# ARS_CR_LedStripModule_Rev1B.net
KiCad netlist of a schematic drawn in Altium Designer
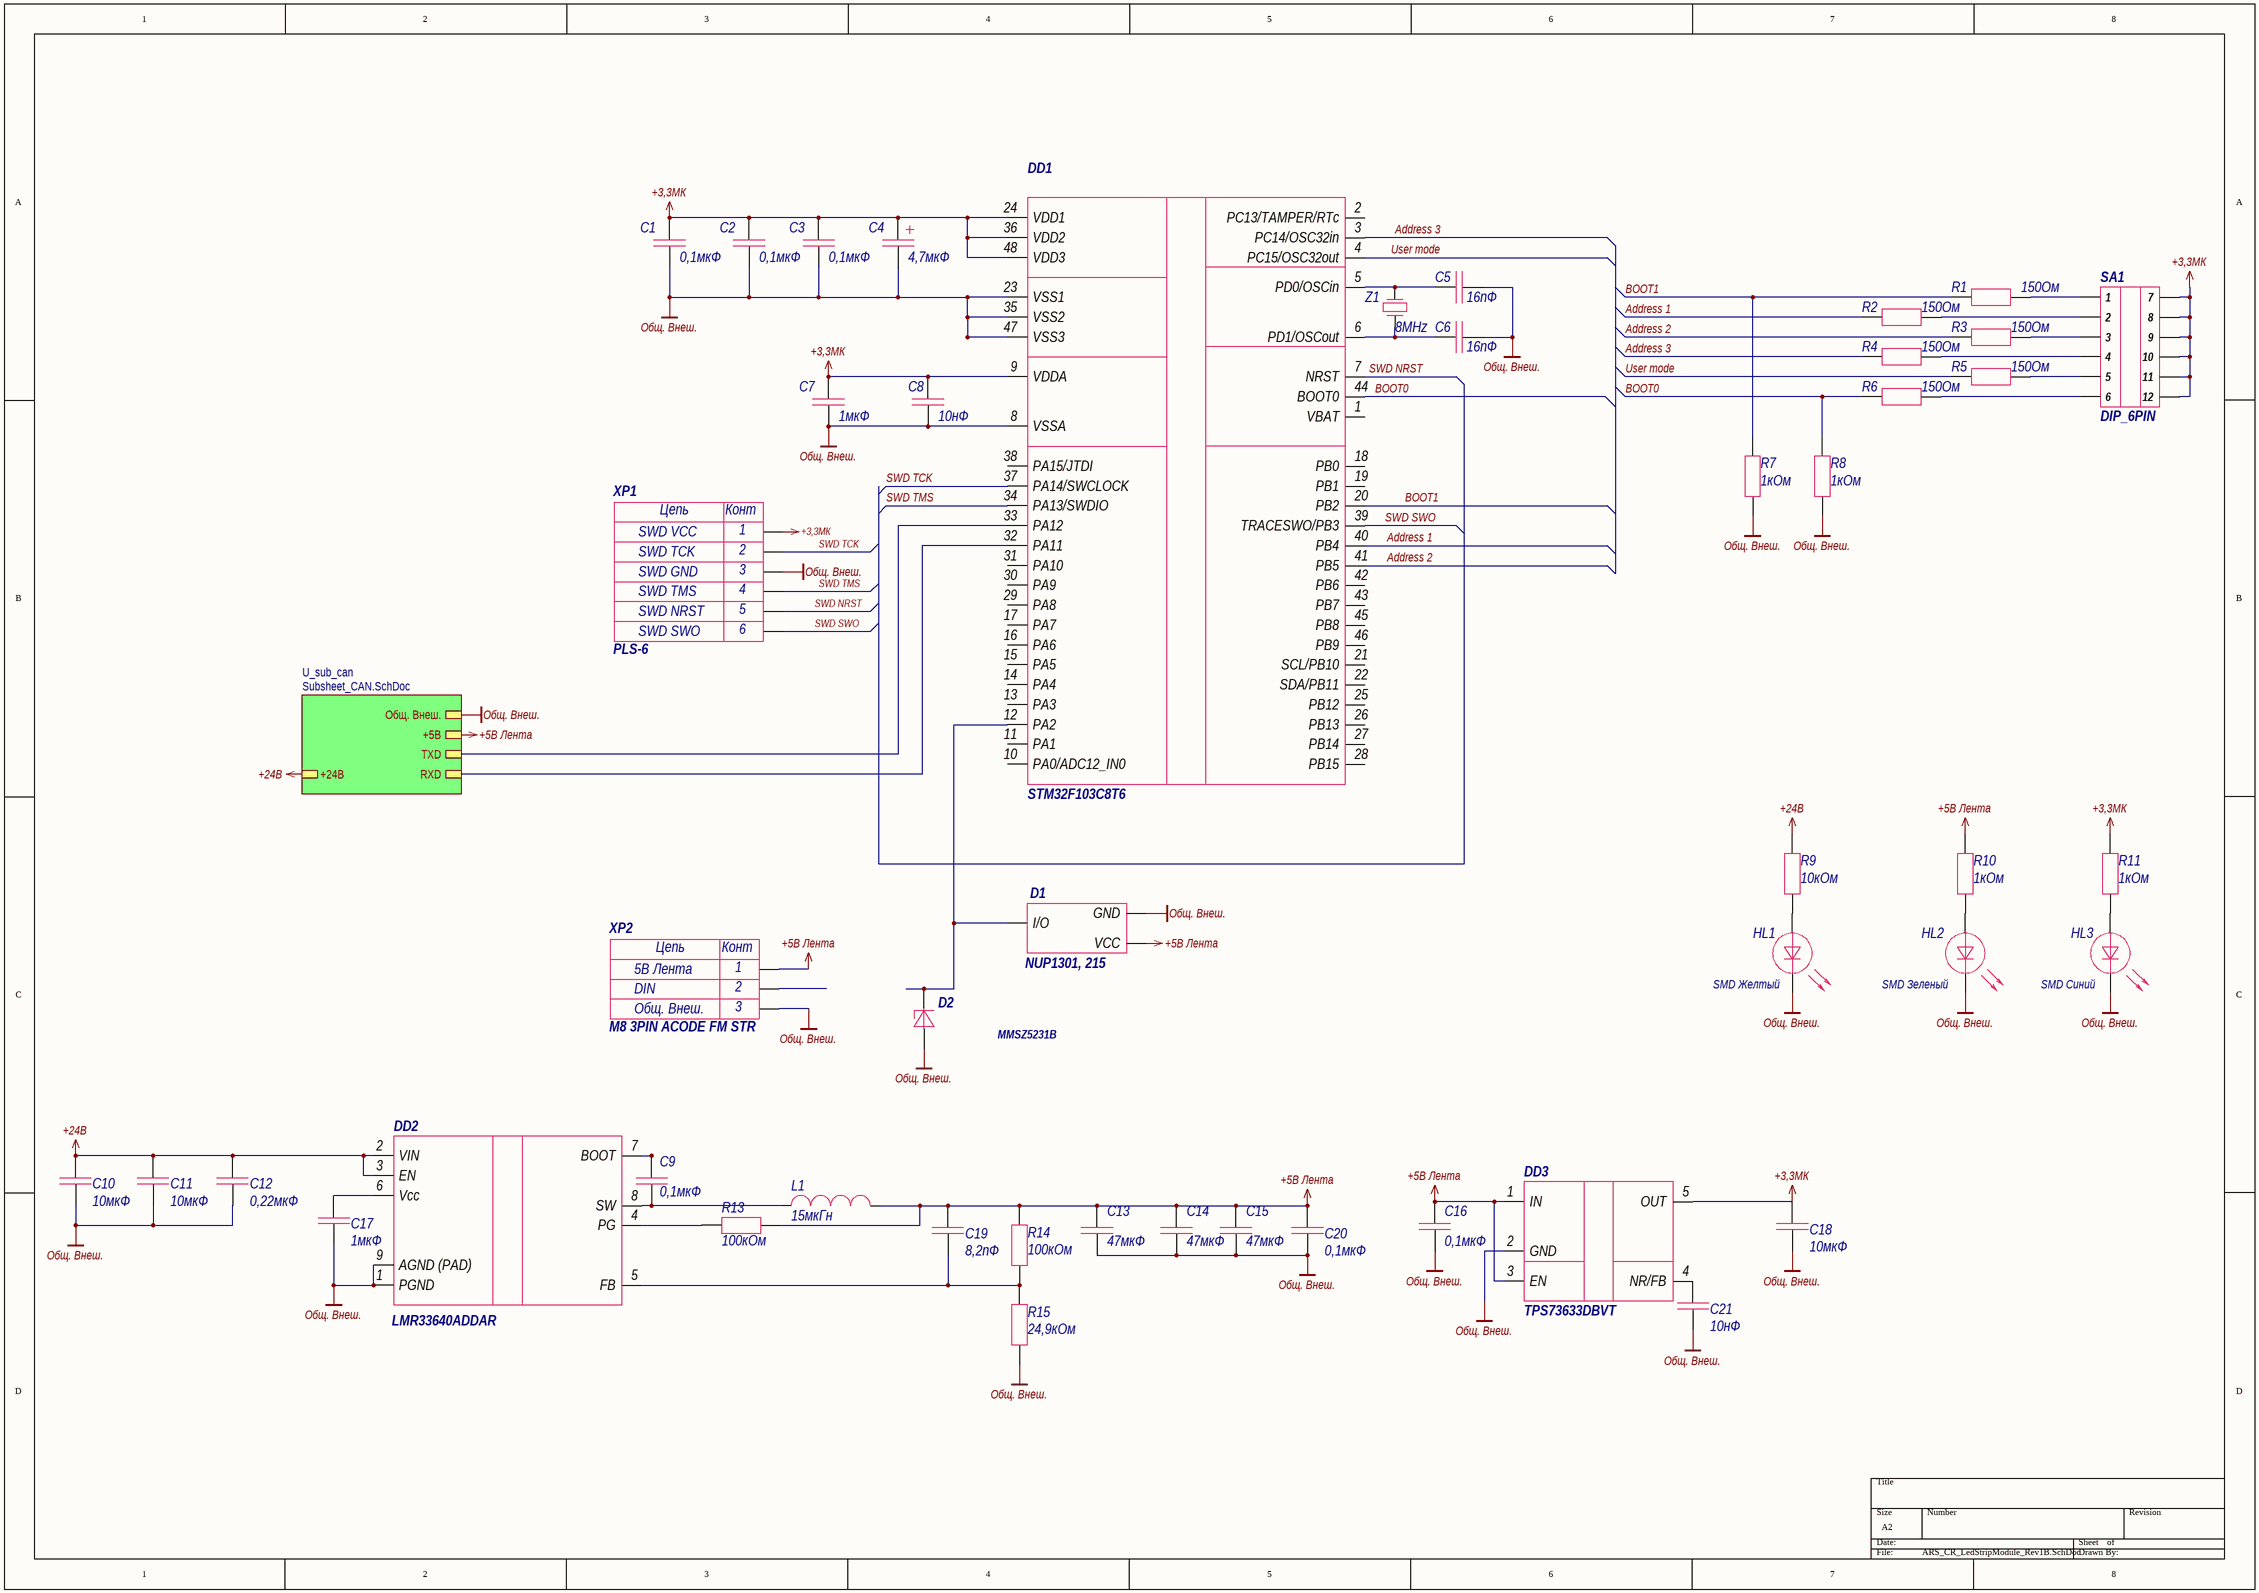
[diagram p0: ARS_CR_LedStripModule_Rev1B.SchDoc]

(export (version "E")
  (design (tool "Eeschema 10.0.6"))
  (components
    (comp (ref "C1")
      (value "0,1мкФ")
      (footprint "0603C")
      (fields (field (name "TOLERANCE") "10%") (field (name "Comment") "Capacitor"))
      (libsource (lib "Database_Maltsev") (part "Capacitor"))
    )
    (comp (ref "C2")
      (value "0,1мкФ")
      (footprint "0603C")
      (fields (field (name "TOLERANCE") "10%") (field (name "Comment") "Capacitor"))
      (libsource (lib "Database_Maltsev") (part "Capacitor"))
    )
    (comp (ref "C3")
      (value "0,1мкФ")
      (footprint "0603C")
      (fields (field (name "TOLERANCE") "10%") (field (name "Comment") "Capacitor"))
      (libsource (lib "Database_Maltsev") (part "Capacitor"))
    )
    (comp (ref "C4")
      (value "4,7мкФ")
      (footprint "TC_A (3216)")
      (fields (field (name "TOLERANCE") "10%") (field (name "Comment") "1uF"))
      (libsource (lib "Database_Maltsev") (part "Capacitor Polarized"))
    )
    (comp (ref "C5")
      (value "16пФ")
      (footprint "0603C")
      (fields (field (name "TOLERANCE") "5%") (field (name "Comment") "Capacitor"))
      (libsource (lib "Database_Maltsev") (part "Capacitor"))
    )
    (comp (ref "C6")
      (value "16пФ")
      (footprint "0603C")
      (fields (field (name "TOLERANCE") "5%") (field (name "Comment") "Capacitor"))
      (libsource (lib "Database_Maltsev") (part "Capacitor"))
    )
    (comp (ref "C7")
      (value "1мкФ")
      (footprint "0603C")
      (fields (field (name "TOLERANCE") "10%") (field (name "Comment") "Capacitor"))
      (libsource (lib "Database_Maltsev") (part "Capacitor"))
    )
    (comp (ref "C8")
      (value "10нФ")
      (footprint "0603C")
      (fields (field (name "TOLERANCE") "10%") (field (name "Comment") "Capacitor"))
      (libsource (lib "Database_Maltsev") (part "Capacitor"))
    )
    (comp (ref "C9")
      (value "0,1мкФ")
      (footprint "0603C")
      (fields (field (name "TOLERANCE") "10%") (field (name "Comment") "Capacitor"))
      (libsource (lib "Database_Maltsev") (part "Capacitor"))
    )
    (comp (ref "C10")
      (value "10мкФ")
      (footprint "1210C")
      (fields (field (name "TOLERANCE") "20%") (field (name "Comment") "Capacitor"))
      (libsource (lib "Database_Maltsev") (part "Capacitor"))
    )
    (comp (ref "C11")
      (value "10мкФ")
      (footprint "1210C")
      (fields (field (name "TOLERANCE") "20%") (field (name "Comment") "Capacitor"))
      (libsource (lib "Database_Maltsev") (part "Capacitor"))
    )
    (comp (ref "C12")
      (value "0,22мкФ")
      (footprint "0603C")
      (fields (field (name "TOLERANCE") "5%") (field (name "Comment") "Capacitor"))
      (libsource (lib "Database_Maltsev") (part "Capacitor"))
    )
    (comp (ref "C13")
      (value "47мкФ")
      (footprint "1210C")
      (fields (field (name "TOLERANCE") "10%") (field (name "Comment") "Capacitor"))
      (libsource (lib "Database_Maltsev") (part "Capacitor"))
    )
    (comp (ref "C14")
      (value "47мкФ")
      (footprint "1210C")
      (fields (field (name "TOLERANCE") "10%") (field (name "Comment") "Capacitor"))
      (libsource (lib "Database_Maltsev") (part "Capacitor"))
    )
    (comp (ref "C15")
      (value "47мкФ")
      (footprint "1210C")
      (fields (field (name "TOLERANCE") "10%") (field (name "Comment") "Capacitor"))
      (libsource (lib "Database_Maltsev") (part "Capacitor"))
    )
    (comp (ref "C16")
      (value "0,1мкФ")
      (footprint "0603C")
      (fields (field (name "TOLERANCE") "10%") (field (name "Comment") "Capacitor"))
      (libsource (lib "Database_Maltsev") (part "Capacitor"))
    )
    (comp (ref "C17")
      (value "1мкФ")
      (footprint "0603C")
      (fields (field (name "TOLERANCE") "10%") (field (name "Comment") "Capacitor"))
      (libsource (lib "Database_Maltsev") (part "Capacitor"))
    )
    (comp (ref "C18")
      (value "10мкФ")
      (footprint "0805C")
      (fields (field (name "TOLERANCE") "10%") (field (name "Comment") "Capacitor"))
      (libsource (lib "Database_Maltsev") (part "Capacitor"))
    )
    (comp (ref "C19")
      (value "8,2пФ")
      (footprint "0603C")
      (fields (field (name "TOLERANCE") "3%") (field (name "Comment") "Capacitor"))
      (libsource (lib "Database_Maltsev") (part "Capacitor"))
    )
    (comp (ref "C20")
      (value "0,1мкФ")
      (footprint "0603C")
      (fields (field (name "TOLERANCE") "10%") (field (name "Comment") "Capacitor"))
      (libsource (lib "Database_Maltsev") (part "Capacitor"))
    )
    (comp (ref "C21")
      (value "10нФ")
      (footprint "0603C")
      (fields (field (name "TOLERANCE") "10%") (field (name "Comment") "Capacitor"))
      (libsource (lib "Database_Maltsev") (part "Capacitor"))
    )
    (comp (ref "D1")
      (value "NUP1301, 215")
      (footprint "SOT23")
      (description "TVS")
      (libsource (lib "Database_Maltsev") (part "NUP1301,215"))
    )
    (comp (ref "D2")
      (value "Zener_Diode")
      (footprint "SOD-123FL")
      (libsource (lib "Database_Maltsev") (part "Zener_Diode"))
    )
    (comp (ref "DD1")
      (value "STM32F103C8T6")
      (footprint "LQFP48")
      (description "STM 32-bit MCU")
      (fields (field (name "DESIGNER STATUS") "Tested and Approved"))
      (libsource (lib "Database_Maltsev") (part "STM32F103C8T6"))
    )
    (comp (ref "DD2")
      (value "LMR33640ADDAR")
      (footprint "SOIC-9N")
      (fields (field (name "PART NAME") "LMR33640ADDAR"))
      (libsource (lib "Database_Maltsev") (part "LMR33640ADDAR"))
    )
    (comp (ref "DD3")
      (value "TPS73633DBVT")
      (footprint "SOT23-5L")
      (fields (field (name "PART NAME") "TPS73633DBVT"))
      (libsource (lib "Database_Maltsev") (part "TPS73633DBVT"))
    )
    (comp (ref "HL1")
      (value "SMD Желтый")
      (footprint "0805D")
      (description "Желтый")
      (libsource (lib "Database_Maltsev") (part "LED"))
    )
    (comp (ref "HL2")
      (value "SMD Зеленый")
      (footprint "0805D")
      (description "Зеленый")
      (libsource (lib "Database_Maltsev") (part "LED"))
    )
    (comp (ref "HL3")
      (value "SMD Синий")
      (footprint "0805D")
      (description "Синий")
      (libsource (lib "Database_Maltsev") (part "LED"))
    )
    (comp (ref "L1")
      (value "15мкГн")
      (footprint "induct_12,3x12,3x8")
      (fields (field (name "TOLERANCE") "20%") (field (name "Comment") "Inductance"))
      (libsource (lib "Database_Maltsev") (part "Inductance"))
    )
    (comp (ref "R1")
      (value "150Ом")
      (footprint "0603R")
      (fields (field (name "TOLERANCE") "1%") (field (name "Comment") "Resistor"))
      (libsource (lib "Database_Maltsev") (part "Resistor"))
    )
    (comp (ref "R2")
      (value "150Ом")
      (footprint "0603R")
      (fields (field (name "TOLERANCE") "1%") (field (name "Comment") "Resistor"))
      (libsource (lib "Database_Maltsev") (part "Resistor"))
    )
    (comp (ref "R3")
      (value "150Ом")
      (footprint "0603R")
      (fields (field (name "TOLERANCE") "1%") (field (name "Comment") "Resistor"))
      (libsource (lib "Database_Maltsev") (part "Resistor"))
    )
    (comp (ref "R4")
      (value "150Ом")
      (footprint "0603R")
      (fields (field (name "TOLERANCE") "1%") (field (name "Comment") "Resistor"))
      (libsource (lib "Database_Maltsev") (part "Resistor"))
    )
    (comp (ref "R5")
      (value "150Ом")
      (footprint "0603R")
      (fields (field (name "TOLERANCE") "1%") (field (name "Comment") "Resistor"))
      (libsource (lib "Database_Maltsev") (part "Resistor"))
    )
    (comp (ref "R6")
      (value "150Ом")
      (footprint "0603R")
      (fields (field (name "TOLERANCE") "1%") (field (name "Comment") "Resistor"))
      (libsource (lib "Database_Maltsev") (part "Resistor"))
    )
    (comp (ref "R7")
      (value "1кОм")
      (footprint "0603R")
      (fields (field (name "TOLERANCE") "5%") (field (name "Comment") "Resistor"))
      (libsource (lib "") (part "Resistor_1"))
    )
    (comp (ref "R8")
      (value "1кОм")
      (footprint "0603R")
      (fields (field (name "TOLERANCE") "5%") (field (name "Comment") "Resistor"))
      (libsource (lib "") (part "Resistor_1"))
    )
    (comp (ref "R9")
      (value "10кОм")
      (footprint "0603R")
      (fields (field (name "TOLERANCE") "5%") (field (name "Comment") "Resistor"))
      (libsource (lib "") (part "Resistor_1"))
    )
    (comp (ref "R10")
      (value "1кОм")
      (footprint "0603R")
      (fields (field (name "TOLERANCE") "5%") (field (name "Comment") "Resistor"))
      (libsource (lib "") (part "Resistor_1"))
    )
    (comp (ref "R11")
      (value "1кОм")
      (footprint "0603R")
      (fields (field (name "TOLERANCE") "5%") (field (name "Comment") "Resistor"))
      (libsource (lib "") (part "Resistor_1"))
    )
    (comp (ref "R13")
      (value "100кОм")
      (footprint "0603R")
      (fields (field (name "TOLERANCE") "1%") (field (name "Comment") "Resistor"))
      (libsource (lib "Database_Maltsev") (part "Resistor"))
    )
    (comp (ref "R14")
      (value "100кОм")
      (footprint "0603R")
      (fields (field (name "TOLERANCE") "1%") (field (name "Comment") "Resistor"))
      (libsource (lib "") (part "Resistor_1"))
    )
    (comp (ref "R15")
      (value "24,9кОм")
      (footprint "0603R")
      (fields (field (name "TOLERANCE") "1%") (field (name "Comment") "Resistor"))
      (libsource (lib "") (part "Resistor_1"))
    )
    (comp (ref "SA1")
      (value "DIP_6PIN")
      (footprint "SW-6")
      (description "SMD")
      (libsource (lib "Database_Maltsev") (part "DIP_6PIN"))
    )
    (comp (ref "XP1")
      (value "PLS-6")
      (footprint "PLS6")
      (description "Male")
      (fields
        (field (name "VALUE1") "SWD VCC")
        (field (name "VALUE2") "SWD TCK")
        (field (name "VALUE3") "SWD GND")
        (field (name "VALUE4") "SWD TMS")
        (field (name "VALUE5") "SWD NRST")
        (field (name "VALUE6") "SWD SWO")
        (field (name "Comment") "6_PIN_XP")
      )
      (libsource (lib "Database_Maltsev") (part "6_PIN_XP"))
    )
    (comp (ref "XP2")
      (value "M8 3PIN ACODE FM STR")
      (footprint "M8_ACODE_3PIN_FM_STR")
      (description "A code ; Female ; Front mount")
      (fields
        (field (name "VALUE1") "5В Лента")
        (field (name "VALUE2") "DIN")
        (field (name "VALUE3") "Общ. Внеш.")
        (field (name "TOLERANCE") "straight")
        (field (name "Comment") "3_PIN_XP")
      )
      (libsource (lib "Database_Maltsev") (part "3_PIN_XP"))
    )
    (comp (ref "Z1")
      (value "8MHz")
      (footprint "HC49US")
      (description "Резонатор")
      (fields (field (name "Comment") "XTAL"))
      (libsource (lib "Database_Maltsev") (part "XTAL"))
    )
  )
  (nets
    (net (code "1") (name "+3,3МК") (class "Default")
      (node (ref "C1") (pin "2") (pinfunction "2_2") (pintype "passive"))
      (node (ref "C18") (pin "2") (pinfunction "2_2") (pintype "passive"))
      (node (ref "C2") (pin "2") (pinfunction "2_2") (pintype "passive"))
      (node (ref "C3") (pin "2") (pinfunction "2_2") (pintype "passive"))
      (node (ref "C4") (pin "1") (pinfunction "1_1") (pintype "passive"))
      (node (ref "C7") (pin "2") (pinfunction "2_2") (pintype "passive"))
      (node (ref "C8") (pin "2") (pinfunction "2_2") (pintype "passive"))
      (node (ref "DD1") (pin "24") (pinfunction "VDD1_24") (pintype "passive"))
      (node (ref "DD1") (pin "36") (pinfunction "VDD2_36") (pintype "passive"))
      (node (ref "DD1") (pin "48") (pinfunction "VDD3_48") (pintype "passive"))
      (node (ref "DD1") (pin "9") (pinfunction "VDDA_9") (pintype "passive"))
      (node (ref "DD3") (pin "5") (pinfunction "OUT_5") (pintype "passive"))
      (node (ref "R11") (pin "2") (pinfunction "2_2") (pintype "passive"))
      (node (ref "SA1") (pin "10") (pinfunction "10_10") (pintype "passive"))
      (node (ref "SA1") (pin "11") (pinfunction "11_11") (pintype "passive"))
      (node (ref "SA1") (pin "12") (pinfunction "12_12") (pintype "passive"))
      (node (ref "SA1") (pin "7") (pinfunction "7_7") (pintype "passive"))
      (node (ref "SA1") (pin "8") (pinfunction "8_8") (pintype "passive"))
      (node (ref "SA1") (pin "9") (pinfunction "9_9") (pintype "passive"))
      (node (ref "XP1") (pin "1") (pinfunction "1_1") (pintype "passive"))
    )
    (net (code "2") (name "+5В Лента") (class "Default")
      (node (ref "C13") (pin "2") (pinfunction "2_2") (pintype "passive"))
      (node (ref "C14") (pin "2") (pinfunction "2_2") (pintype "passive"))
      (node (ref "C15") (pin "2") (pinfunction "2_2") (pintype "passive"))
      (node (ref "C16") (pin "2") (pinfunction "2_2") (pintype "passive"))
      (node (ref "C19") (pin "2") (pinfunction "2_2") (pintype "passive"))
      (node (ref "C20") (pin "2") (pinfunction "2_2") (pintype "passive"))
      (node (ref "D1") (pin "2") (pinfunction "VCC_2") (pintype "passive"))
      (node (ref "DD3") (pin "1") (pinfunction "IN_1") (pintype "passive"))
      (node (ref "DD3") (pin "3") (pinfunction "EN_3") (pintype "passive"))
      (node (ref "L1") (pin "2") (pinfunction "2_2") (pintype "passive"))
      (node (ref "R10") (pin "2") (pinfunction "2_2") (pintype "passive"))
      (node (ref "R13") (pin "2") (pinfunction "2_2") (pintype "passive"))
      (node (ref "R14") (pin "2") (pinfunction "2_2") (pintype "passive"))
      (node (ref "XP2") (pin "1") (pinfunction "1_1") (pintype "passive"))
    )
    (net (code "3") (name "+24В") (class "Default")
      (node (ref "C10") (pin "2") (pinfunction "2_2") (pintype "passive"))
      (node (ref "C11") (pin "2") (pinfunction "2_2") (pintype "passive"))
      (node (ref "C12") (pin "2") (pinfunction "2_2") (pintype "passive"))
      (node (ref "DD2") (pin "2") (pinfunction "VIN_2") (pintype "passive"))
      (node (ref "DD2") (pin "3") (pinfunction "EN_3") (pintype "passive"))
      (node (ref "R9") (pin "2") (pinfunction "2_2") (pintype "passive"))
    )
    (net (code "4") (name "/Address 1") (class "Default")
      (node (ref "DD1") (pin "40") (pinfunction "PB4_40") (pintype "passive"))
      (node (ref "R2") (pin "1") (pinfunction "1_1") (pintype "passive"))
    )
    (net (code "5") (name "/Address 2") (class "Default")
      (node (ref "DD1") (pin "41") (pinfunction "PB5_41") (pintype "passive"))
      (node (ref "R3") (pin "1") (pinfunction "1_1") (pintype "passive"))
    )
    (net (code "6") (name "/Address 3") (class "Default")
      (node (ref "DD1") (pin "3") (pinfunction "PC14/OSC32in_3") (pintype "passive"))
      (node (ref "R4") (pin "1") (pinfunction "1_1") (pintype "passive"))
    )
    (net (code "7") (name "/BOOT0") (class "Default")
      (node (ref "DD1") (pin "44") (pinfunction "BOOT0_44") (pintype "passive"))
      (node (ref "R6") (pin "1") (pinfunction "1_1") (pintype "passive"))
      (node (ref "R8") (pin "2") (pinfunction "2_2") (pintype "passive"))
    )
    (net (code "8") (name "/BOOT1") (class "Default")
      (node (ref "DD1") (pin "20") (pinfunction "PB2_20") (pintype "passive"))
      (node (ref "R1") (pin "1") (pinfunction "1_1") (pintype "passive"))
      (node (ref "R7") (pin "2") (pinfunction "2_2") (pintype "passive"))
    )
    (net (code "9") (name "/RXD") (class "Default")
      (node (ref "DD1") (pin "32") (pinfunction "PA11_32") (pintype "passive"))
    )
    (net (code "10") (name "/SWD NRST") (class "Default")
      (node (ref "DD1") (pin "7") (pinfunction "NRST_7") (pintype "passive"))
      (node (ref "XP1") (pin "5") (pinfunction "5_5") (pintype "passive"))
    )
    (net (code "11") (name "/SWD SWO") (class "Default")
      (node (ref "DD1") (pin "39") (pinfunction "TRACESWO/PB3_39") (pintype "passive"))
      (node (ref "XP1") (pin "6") (pinfunction "6_6") (pintype "passive"))
    )
    (net (code "12") (name "/SWD TCK") (class "Default")
      (node (ref "DD1") (pin "37") (pinfunction "PA14/SWCLOCK_37") (pintype "passive"))
      (node (ref "XP1") (pin "2") (pinfunction "2_2") (pintype "passive"))
    )
    (net (code "13") (name "/SWD TMS") (class "Default")
      (node (ref "DD1") (pin "34") (pinfunction "PA13/SWDIO_34") (pintype "passive"))
      (node (ref "XP1") (pin "4") (pinfunction "4_4") (pintype "passive"))
    )
    (net (code "14") (name "/TXD") (class "Default")
      (node (ref "DD1") (pin "33") (pinfunction "PA12_33") (pintype "passive"))
    )
    (net (code "15") (name "/User mode") (class "Default")
      (node (ref "DD1") (pin "4") (pinfunction "PC15/OSC32out_4") (pintype "passive"))
      (node (ref "R5") (pin "1") (pinfunction "1_1") (pintype "passive"))
    )
    (net (code "16") (name "Net-(D1-I{slash}O)") (class "Default")
      (node (ref "D1") (pin "3") (pinfunction "I/O_3") (pintype "passive"))
      (node (ref "D2") (pin "2") (pinfunction "2_2") (pintype "passive"))
      (node (ref "DD1") (pin "12") (pinfunction "PA2_12") (pintype "passive"))
    )
    (net (code "17") (name "Net-(DD1-PD0{slash}OSCin)") (class "Default")
      (node (ref "C5") (pin "2") (pinfunction "2_2") (pintype "passive"))
      (node (ref "DD1") (pin "5") (pinfunction "PD0/OSCin_5") (pintype "passive"))
      (node (ref "Z1") (pin "2") (pinfunction "2_2") (pintype "passive"))
    )
    (net (code "18") (name "Net-(DD1-PD1{slash}OSCout)") (class "Default")
      (node (ref "C6") (pin "2") (pinfunction "2_2") (pintype "passive"))
      (node (ref "DD1") (pin "6") (pinfunction "PD1/OSCout_6") (pintype "passive"))
      (node (ref "Z1") (pin "1") (pinfunction "1_1") (pintype "passive"))
    )
    (net (code "19") (name "Net-(DD2-BOOT)") (class "Default")
      (node (ref "C9") (pin "2") (pinfunction "2_2") (pintype "passive"))
      (node (ref "DD2") (pin "7") (pinfunction "BOOT_7") (pintype "passive"))
    )
    (net (code "20") (name "Net-(DD2-FB)") (class "Default")
      (node (ref "C19") (pin "1") (pinfunction "1_1") (pintype "passive"))
      (node (ref "DD2") (pin "5") (pinfunction "FB_5") (pintype "passive"))
      (node (ref "R14") (pin "1") (pinfunction "1_1") (pintype "passive"))
      (node (ref "R15") (pin "2") (pinfunction "2_2") (pintype "passive"))
    )
    (net (code "21") (name "Net-(DD2-PG)") (class "Default")
      (node (ref "DD2") (pin "4") (pinfunction "PG_4") (pintype "passive"))
      (node (ref "R13") (pin "1") (pinfunction "1_1") (pintype "passive"))
    )
    (net (code "22") (name "Net-(DD2-SW)") (class "Default")
      (node (ref "C9") (pin "1") (pinfunction "1_1") (pintype "passive"))
      (node (ref "DD2") (pin "8") (pinfunction "SW_8") (pintype "passive"))
      (node (ref "L1") (pin "1") (pinfunction "1_1") (pintype "passive"))
    )
    (net (code "23") (name "Net-(DD2-Vcc)") (class "Default")
      (node (ref "C17") (pin "2") (pinfunction "2_2") (pintype "passive"))
      (node (ref "DD2") (pin "6") (pinfunction "Vcc_6") (pintype "passive"))
    )
    (net (code "24") (name "Net-(DD3-NR{slash}FB)") (class "Default")
      (node (ref "C21") (pin "2") (pinfunction "2_2") (pintype "passive"))
      (node (ref "DD3") (pin "4") (pinfunction "NR/FB_4") (pintype "passive"))
    )
    (net (code "25") (name "Net-(HL1-Pad1)") (class "Default")
      (node (ref "HL1") (pin "1") (pinfunction "1_1") (pintype "passive"))
      (node (ref "R9") (pin "1") (pinfunction "1_1") (pintype "passive"))
    )
    (net (code "26") (name "Net-(HL2-Pad1)") (class "Default")
      (node (ref "HL2") (pin "1") (pinfunction "1_1") (pintype "passive"))
      (node (ref "R10") (pin "1") (pinfunction "1_1") (pintype "passive"))
    )
    (net (code "27") (name "Net-(HL3-Pad1)") (class "Default")
      (node (ref "HL3") (pin "1") (pinfunction "1_1") (pintype "passive"))
      (node (ref "R11") (pin "1") (pinfunction "1_1") (pintype "passive"))
    )
    (net (code "28") (name "Net-(R1-Pad2)") (class "Default")
      (node (ref "R1") (pin "2") (pinfunction "2_2") (pintype "passive"))
      (node (ref "SA1") (pin "1") (pinfunction "1_1") (pintype "passive"))
    )
    (net (code "29") (name "Net-(R2-Pad2)") (class "Default")
      (node (ref "R2") (pin "2") (pinfunction "2_2") (pintype "passive"))
      (node (ref "SA1") (pin "2") (pinfunction "2_2") (pintype "passive"))
    )
    (net (code "30") (name "Net-(R3-Pad2)") (class "Default")
      (node (ref "R3") (pin "2") (pinfunction "2_2") (pintype "passive"))
      (node (ref "SA1") (pin "3") (pinfunction "3_3") (pintype "passive"))
    )
    (net (code "31") (name "Net-(R4-Pad2)") (class "Default")
      (node (ref "R4") (pin "2") (pinfunction "2_2") (pintype "passive"))
      (node (ref "SA1") (pin "4") (pinfunction "4_4") (pintype "passive"))
    )
    (net (code "32") (name "Net-(R5-Pad2)") (class "Default")
      (node (ref "R5") (pin "2") (pinfunction "2_2") (pintype "passive"))
      (node (ref "SA1") (pin "5") (pinfunction "5_5") (pintype "passive"))
    )
    (net (code "33") (name "Net-(R6-Pad2)") (class "Default")
      (node (ref "R6") (pin "2") (pinfunction "2_2") (pintype "passive"))
      (node (ref "SA1") (pin "6") (pinfunction "6_6") (pintype "passive"))
    )
    (net (code "34") (name "unconnected-(DD1-PA0{slash}ADC12_IN0-Pad10)") (class "Default")
      (node (ref "DD1") (pin "10") (pinfunction "PA0/ADC12_IN0_10") (pintype "passive"))
    )
    (net (code "35") (name "unconnected-(DD1-PA1-Pad11)") (class "Default")
      (node (ref "DD1") (pin "11") (pinfunction "PA1_11") (pintype "passive"))
    )
    (net (code "36") (name "unconnected-(DD1-PA3-Pad13)") (class "Default")
      (node (ref "DD1") (pin "13") (pinfunction "PA3_13") (pintype "passive"))
    )
    (net (code "37") (name "unconnected-(DD1-PA4-Pad14)") (class "Default")
      (node (ref "DD1") (pin "14") (pinfunction "PA4_14") (pintype "passive"))
    )
    (net (code "38") (name "unconnected-(DD1-PA5-Pad15)") (class "Default")
      (node (ref "DD1") (pin "15") (pinfunction "PA5_15") (pintype "passive"))
    )
    (net (code "39") (name "unconnected-(DD1-PA6-Pad16)") (class "Default")
      (node (ref "DD1") (pin "16") (pinfunction "PA6_16") (pintype "passive"))
    )
    (net (code "40") (name "unconnected-(DD1-PA7-Pad17)") (class "Default")
      (node (ref "DD1") (pin "17") (pinfunction "PA7_17") (pintype "passive"))
    )
    (net (code "41") (name "unconnected-(DD1-PA8-Pad29)") (class "Default")
      (node (ref "DD1") (pin "29") (pinfunction "PA8_29") (pintype "passive"))
    )
    (net (code "42") (name "unconnected-(DD1-PA9-Pad30)") (class "Default")
      (node (ref "DD1") (pin "30") (pinfunction "PA9_30") (pintype "passive"))
    )
    (net (code "43") (name "unconnected-(DD1-PA10-Pad31)") (class "Default")
      (node (ref "DD1") (pin "31") (pinfunction "PA10_31") (pintype "passive"))
    )
    (net (code "44") (name "unconnected-(DD1-PA15{slash}JTDI-Pad38)") (class "Default")
      (node (ref "DD1") (pin "38") (pinfunction "PA15/JTDI_38") (pintype "passive"))
    )
    (net (code "45") (name "unconnected-(DD1-PB0-Pad18)") (class "Default")
      (node (ref "DD1") (pin "18") (pinfunction "PB0_18") (pintype "passive"))
    )
    (net (code "46") (name "unconnected-(DD1-PB1-Pad19)") (class "Default")
      (node (ref "DD1") (pin "19") (pinfunction "PB1_19") (pintype "passive"))
    )
    (net (code "47") (name "unconnected-(DD1-PB6-Pad42)") (class "Default")
      (node (ref "DD1") (pin "42") (pinfunction "PB6_42") (pintype "passive"))
    )
    (net (code "48") (name "unconnected-(DD1-PB7-Pad43)") (class "Default")
      (node (ref "DD1") (pin "43") (pinfunction "PB7_43") (pintype "passive"))
    )
    (net (code "49") (name "unconnected-(DD1-PB8-Pad45)") (class "Default")
      (node (ref "DD1") (pin "45") (pinfunction "PB8_45") (pintype "passive"))
    )
    (net (code "50") (name "unconnected-(DD1-PB9-Pad46)") (class "Default")
      (node (ref "DD1") (pin "46") (pinfunction "PB9_46") (pintype "passive"))
    )
    (net (code "51") (name "unconnected-(DD1-PB12-Pad25)") (class "Default")
      (node (ref "DD1") (pin "25") (pinfunction "PB12_25") (pintype "passive"))
    )
    (net (code "52") (name "unconnected-(DD1-PB13-Pad26)") (class "Default")
      (node (ref "DD1") (pin "26") (pinfunction "PB13_26") (pintype "passive"))
    )
    (net (code "53") (name "unconnected-(DD1-PB14-Pad27)") (class "Default")
      (node (ref "DD1") (pin "27") (pinfunction "PB14_27") (pintype "passive"))
    )
    (net (code "54") (name "unconnected-(DD1-PB15-Pad28)") (class "Default")
      (node (ref "DD1") (pin "28") (pinfunction "PB15_28") (pintype "passive"))
    )
    (net (code "55") (name "unconnected-(DD1-PC13{slash}TAMPER{slash}RTc-Pad2)") (class "Default")
      (node (ref "DD1") (pin "2") (pinfunction "PC13/TAMPER/RTc_2") (pintype "passive"))
    )
    (net (code "56") (name "unconnected-(DD1-SCL{slash}PB10-Pad21)") (class "Default")
      (node (ref "DD1") (pin "21") (pinfunction "SCL/PB10_21") (pintype "passive"))
    )
    (net (code "57") (name "unconnected-(DD1-SDA{slash}PB11-Pad22)") (class "Default")
      (node (ref "DD1") (pin "22") (pinfunction "SDA/PB11_22") (pintype "passive"))
    )
    (net (code "58") (name "unconnected-(DD1-VBAT-Pad1)") (class "Default")
      (node (ref "DD1") (pin "1") (pinfunction "VBAT_1") (pintype "passive"))
    )
    (net (code "59") (name "unconnected-(XP2-Pad2)") (class "Default")
      (node (ref "XP2") (pin "2") (pinfunction "2_2") (pintype "passive"))
    )
    (net (code "60") (name "Общ. Внеш.") (class "Default")
      (node (ref "C1") (pin "1") (pinfunction "1_1") (pintype "passive"))
      (node (ref "C10") (pin "1") (pinfunction "1_1") (pintype "passive"))
      (node (ref "C11") (pin "1") (pinfunction "1_1") (pintype "passive"))
      (node (ref "C12") (pin "1") (pinfunction "1_1") (pintype "passive"))
      (node (ref "C13") (pin "1") (pinfunction "1_1") (pintype "passive"))
      (node (ref "C14") (pin "1") (pinfunction "1_1") (pintype "passive"))
      (node (ref "C15") (pin "1") (pinfunction "1_1") (pintype "passive"))
      (node (ref "C16") (pin "1") (pinfunction "1_1") (pintype "passive"))
      (node (ref "C17") (pin "1") (pinfunction "1_1") (pintype "passive"))
      (node (ref "C18") (pin "1") (pinfunction "1_1") (pintype "passive"))
      (node (ref "C2") (pin "1") (pinfunction "1_1") (pintype "passive"))
      (node (ref "C20") (pin "1") (pinfunction "1_1") (pintype "passive"))
      (node (ref "C21") (pin "1") (pinfunction "1_1") (pintype "passive"))
      (node (ref "C3") (pin "1") (pinfunction "1_1") (pintype "passive"))
      (node (ref "C4") (pin "2") (pinfunction "2_2") (pintype "passive"))
      (node (ref "C5") (pin "1") (pinfunction "1_1") (pintype "passive"))
      (node (ref "C6") (pin "1") (pinfunction "1_1") (pintype "passive"))
      (node (ref "C7") (pin "1") (pinfunction "1_1") (pintype "passive"))
      (node (ref "C8") (pin "1") (pinfunction "1_1") (pintype "passive"))
      (node (ref "D1") (pin "1") (pinfunction "GND_1") (pintype "passive"))
      (node (ref "D2") (pin "1") (pinfunction "1_1") (pintype "passive"))
      (node (ref "DD1") (pin "23") (pinfunction "VSS1_23") (pintype "passive"))
      (node (ref "DD1") (pin "35") (pinfunction "VSS2_35") (pintype "passive"))
      (node (ref "DD1") (pin "47") (pinfunction "VSS3_47") (pintype "passive"))
      (node (ref "DD1") (pin "8") (pinfunction "VSSA_8") (pintype "passive"))
      (node (ref "DD2") (pin "1") (pinfunction "PGND_1") (pintype "passive"))
      (node (ref "DD2") (pin "9") (pinfunction "AGND_(PAD)_9") (pintype "passive"))
      (node (ref "DD3") (pin "2") (pinfunction "GND_2") (pintype "passive"))
      (node (ref "HL1") (pin "2") (pinfunction "2_2") (pintype "passive"))
      (node (ref "HL2") (pin "2") (pinfunction "2_2") (pintype "passive"))
      (node (ref "HL3") (pin "2") (pinfunction "2_2") (pintype "passive"))
      (node (ref "R15") (pin "1") (pinfunction "1_1") (pintype "passive"))
      (node (ref "R7") (pin "1") (pinfunction "1_1") (pintype "passive"))
      (node (ref "R8") (pin "1") (pinfunction "1_1") (pintype "passive"))
      (node (ref "XP1") (pin "3") (pinfunction "3_3") (pintype "passive"))
      (node (ref "XP2") (pin "3") (pinfunction "3_3") (pintype "passive"))
    )
  )
)
